# pocket_scope_complete_adc_v0001.net
KiCad netlist of a schematic drawn in EAGLE
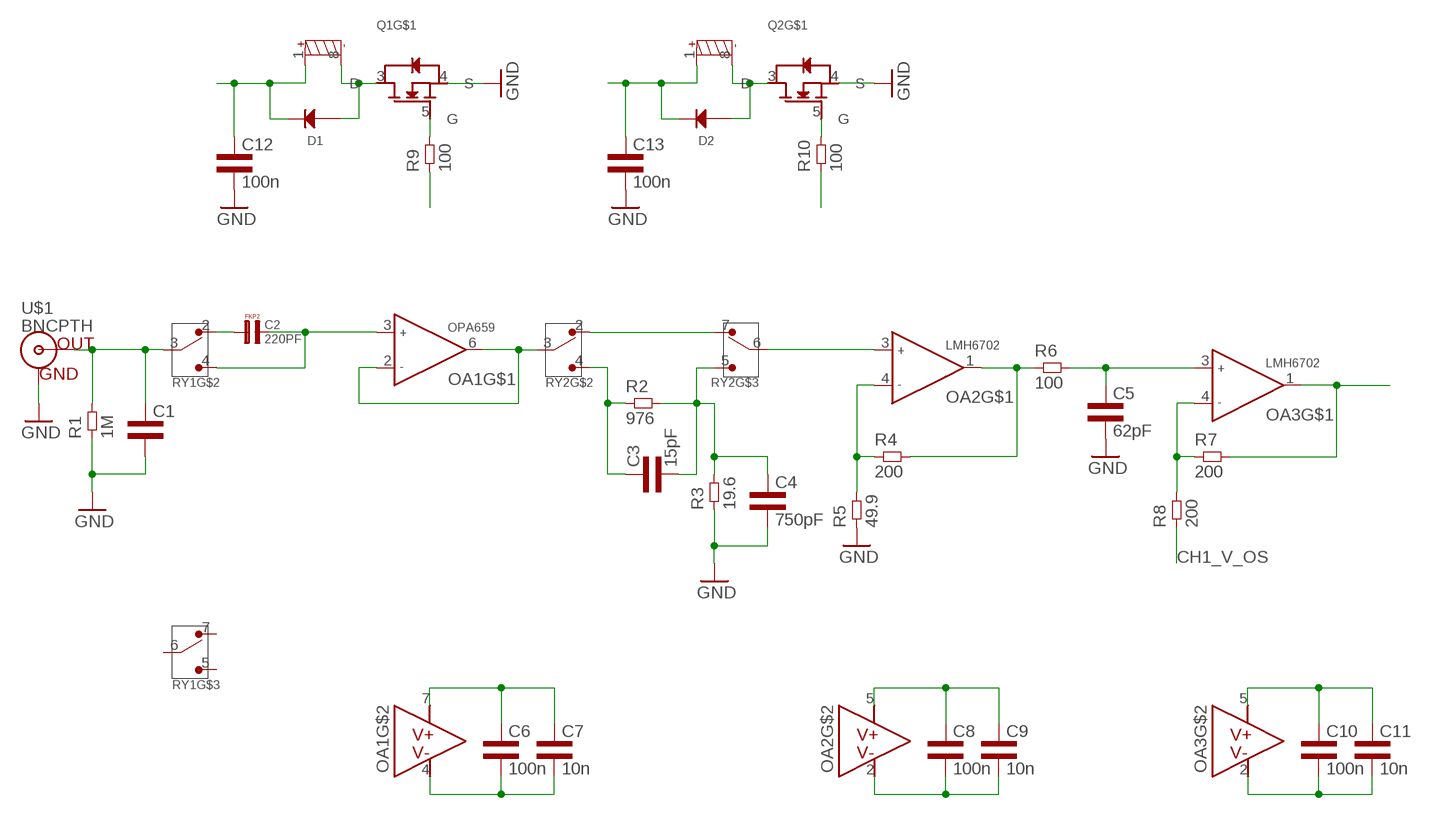
[diagram p0: schematic, sheet 1]

(export (version "E")
  (design (tool "Eeschema 10.0.6"))
  (components
    (comp (ref "C1")
      (value "CAP0603L3")
      (footprint "eagle-import:0603L3")
      (libsource (lib "eagle-import") (part "CAP0603L3"))
    )
    (comp (ref "C2")
      (value "220PF")
      (footprint "eagle-import:R5B4K5")
      (libsource (lib "eagle-import") (part "220PF"))
    )
    (comp (ref "C3")
      (value "15pF")
      (footprint "eagle-import:0603L3")
      (libsource (lib "eagle-import") (part "CAP0603L3"))
    )
    (comp (ref "C4")
      (value "750pF")
      (footprint "eagle-import:0603L3")
      (libsource (lib "eagle-import") (part "CAP0603L3"))
    )
    (comp (ref "C5")
      (value "62pF")
      (footprint "eagle-import:0603L3")
      (libsource (lib "eagle-import") (part "CAP0603L3"))
    )
    (comp (ref "C6")
      (value "100n")
      (footprint "eagle-import:0603L3")
      (libsource (lib "eagle-import") (part "CAP0603L3"))
    )
    (comp (ref "C7")
      (value "10n")
      (footprint "eagle-import:0603L3")
      (libsource (lib "eagle-import") (part "CAP0603L3"))
    )
    (comp (ref "C8")
      (value "100n")
      (footprint "eagle-import:0603L3")
      (libsource (lib "eagle-import") (part "CAP0603L3"))
    )
    (comp (ref "C9")
      (value "10n")
      (footprint "eagle-import:0603L3")
      (libsource (lib "eagle-import") (part "CAP0603L3"))
    )
    (comp (ref "C10")
      (value "100n")
      (footprint "eagle-import:0603L3")
      (libsource (lib "eagle-import") (part "CAP0603L3"))
    )
    (comp (ref "C11")
      (value "10n")
      (footprint "eagle-import:0603L3")
      (libsource (lib "eagle-import") (part "CAP0603L3"))
    )
    (comp (ref "C12")
      (value "100n")
      (footprint "eagle-import:0603L3")
      (libsource (lib "eagle-import") (part "CAP0603L3"))
    )
    (comp (ref "C13")
      (value "100n")
      (footprint "eagle-import:0603L3")
      (libsource (lib "eagle-import") (part "CAP0603L3"))
    )
    (comp (ref "D1")
      (value "DIODESMA")
      (footprint "eagle-import:SMA-2")
      (libsource (lib "eagle-import") (part "DIODESMA"))
    )
    (comp (ref "D2")
      (value "DIODESMA")
      (footprint "eagle-import:SMA-2")
      (libsource (lib "eagle-import") (part "DIODESMA"))
    )
    (comp (ref "OA1")
      (value "OPA659")
      (footprint "eagle-import:S-PVSON-N8")
      (libsource (lib "eagle-import") (part "OPA659DRB"))
    )
    (comp (ref "OA2")
      (value "LMH6702")
      (footprint "eagle-import:R-PDSO-G5")
      (libsource (lib "eagle-import") (part "OPA659DBV"))
    )
    (comp (ref "OA3")
      (value "LMH6702")
      (footprint "eagle-import:R-PDSO-G5")
      (libsource (lib "eagle-import") (part "OPA659DBV"))
    )
    (comp (ref "Q1")
      (value "2N7002DWA")
      (footprint "eagle-import:SC70")
      (libsource (lib "eagle-import") (part "2N7002DWA"))
    )
    (comp (ref "Q2")
      (value "2N7002DWA")
      (footprint "eagle-import:SC70")
      (libsource (lib "eagle-import") (part "2N7002DWA"))
    )
    (comp (ref "R1")
      (value "1M")
      (footprint "eagle-import:0603L3")
      (libsource (lib "eagle-import") (part "RES0603L3"))
    )
    (comp (ref "R2")
      (value "976")
      (footprint "eagle-import:0603L3")
      (libsource (lib "eagle-import") (part "RES0603L3"))
    )
    (comp (ref "R3")
      (value "19.6")
      (footprint "eagle-import:0603L3")
      (libsource (lib "eagle-import") (part "RES0603L3"))
    )
    (comp (ref "R4")
      (value "200")
      (footprint "eagle-import:0603L3")
      (libsource (lib "eagle-import") (part "RES0603L3"))
    )
    (comp (ref "R5")
      (value "49.9")
      (footprint "eagle-import:0603L3")
      (libsource (lib "eagle-import") (part "RES0603L3"))
    )
    (comp (ref "R6")
      (value "100")
      (footprint "eagle-import:0603L3")
      (libsource (lib "eagle-import") (part "RES0603L3"))
    )
    (comp (ref "R7")
      (value "200")
      (footprint "eagle-import:0603L3")
      (libsource (lib "eagle-import") (part "RES0603L3"))
    )
    (comp (ref "R8")
      (value "200")
      (footprint "eagle-import:0603L3")
      (libsource (lib "eagle-import") (part "RES0603L3"))
    )
    (comp (ref "R9")
      (value "100")
      (footprint "eagle-import:0603L3")
      (libsource (lib "eagle-import") (part "RES0603L3"))
    )
    (comp (ref "R10")
      (value "100")
      (footprint "eagle-import:0603L3")
      (libsource (lib "eagle-import") (part "RES0603L3"))
    )
    (comp (ref "RY1")
      (value "RELAY_SMD")
      (footprint "eagle-import:G6J-2FL-Y")
      (libsource (lib "eagle-import") (part "RELAY_SMD"))
    )
    (comp (ref "RY2")
      (value "RELAY_SMD")
      (footprint "eagle-import:G6J-2FL-Y")
      (libsource (lib "eagle-import") (part "RELAY_SMD"))
    )
    (comp (ref "U$1")
      (value "BNCPTH")
      (footprint "eagle-import:BNC")
      (libsource (lib "eagle-import") (part "BNCPTH"))
    )
  )
  (nets
    (net (code "1") (name "/CH1_V_OS") (class "Default")
      (node (ref "R8") (pin "P$1") (pinfunction "1_P$1") (pintype "bidirectional"))
    )
    (net (code "2") (name "GND") (class "Default")
      (node (ref "C1") (pin "P$2") (pinfunction "2_P$2") (pintype "bidirectional"))
      (node (ref "C12") (pin "P$2") (pinfunction "2_P$2") (pintype "bidirectional"))
      (node (ref "C13") (pin "P$2") (pinfunction "2_P$2") (pintype "bidirectional"))
      (node (ref "C4") (pin "P$2") (pinfunction "2_P$2") (pintype "bidirectional"))
      (node (ref "C5") (pin "P$2") (pinfunction "2_P$2") (pintype "bidirectional"))
      (node (ref "Q1") (pin "4") (pinfunction "S_4") (pintype "bidirectional"))
      (node (ref "Q2") (pin "4") (pinfunction "S_4") (pintype "bidirectional"))
      (node (ref "R1") (pin "P$1") (pinfunction "1_P$1") (pintype "bidirectional"))
      (node (ref "R3") (pin "P$1") (pinfunction "1_P$1") (pintype "bidirectional"))
      (node (ref "R5") (pin "P$1") (pinfunction "1_P$1") (pintype "bidirectional"))
      (node (ref "U$1") (pin "GND") (pinfunction "GND_GND") (pintype "bidirectional"))
    )
    (net (code "3") (name "Net-(C1-1)") (class "Default")
      (node (ref "C1") (pin "P$1") (pinfunction "1_P$1") (pintype "bidirectional"))
      (node (ref "R1") (pin "P$2") (pinfunction "2_P$2") (pintype "bidirectional"))
      (node (ref "RY1") (pin "3") (pinfunction "D_3") (pintype "bidirectional"))
      (node (ref "U$1") (pin "S") (pinfunction "OUT_S") (pintype "bidirectional"))
    )
    (net (code "4") (name "Net-(C3-1)") (class "Default")
      (node (ref "C3") (pin "P$1") (pinfunction "1_P$1") (pintype "bidirectional"))
      (node (ref "R2") (pin "P$1") (pinfunction "1_P$1") (pintype "bidirectional"))
      (node (ref "RY2") (pin "4") (pinfunction "T2_4") (pintype "bidirectional"))
    )
    (net (code "5") (name "Net-(C3-2)") (class "Default")
      (node (ref "C3") (pin "P$2") (pinfunction "2_P$2") (pintype "bidirectional"))
      (node (ref "C4") (pin "P$1") (pinfunction "1_P$1") (pintype "bidirectional"))
      (node (ref "R2") (pin "P$2") (pinfunction "2_P$2") (pintype "bidirectional"))
      (node (ref "R3") (pin "P$2") (pinfunction "2_P$2") (pintype "bidirectional"))
      (node (ref "RY2") (pin "5") (pinfunction "T2_5") (pintype "bidirectional"))
    )
    (net (code "6") (name "Net-(C5-1)") (class "Default")
      (node (ref "C5") (pin "P$1") (pinfunction "1_P$1") (pintype "bidirectional"))
      (node (ref "OA3") (pin "3") (pinfunction "INA+_3") (pintype "bidirectional"))
      (node (ref "R6") (pin "P$2") (pinfunction "2_P$2") (pintype "bidirectional"))
    )
    (net (code "7") (name "Net-(C6-1)") (class "Default")
      (node (ref "C6") (pin "P$1") (pinfunction "1_P$1") (pintype "bidirectional"))
      (node (ref "C7") (pin "P$1") (pinfunction "1_P$1") (pintype "bidirectional"))
      (node (ref "OA1") (pin "7") (pinfunction "V+_7") (pintype "power_in"))
    )
    (net (code "8") (name "Net-(C6-2)") (class "Default")
      (node (ref "C6") (pin "P$2") (pinfunction "2_P$2") (pintype "bidirectional"))
      (node (ref "C7") (pin "P$2") (pinfunction "2_P$2") (pintype "bidirectional"))
      (node (ref "OA1") (pin "4") (pinfunction "V-_4") (pintype "power_in"))
    )
    (net (code "9") (name "Net-(C8-1)") (class "Default")
      (node (ref "C8") (pin "P$1") (pinfunction "1_P$1") (pintype "bidirectional"))
      (node (ref "C9") (pin "P$1") (pinfunction "1_P$1") (pintype "bidirectional"))
      (node (ref "OA2") (pin "5") (pinfunction "V+_5") (pintype "power_in"))
    )
    (net (code "10") (name "Net-(C8-2)") (class "Default")
      (node (ref "C8") (pin "P$2") (pinfunction "2_P$2") (pintype "bidirectional"))
      (node (ref "C9") (pin "P$2") (pinfunction "2_P$2") (pintype "bidirectional"))
      (node (ref "OA2") (pin "2") (pinfunction "V-_2") (pintype "power_in"))
    )
    (net (code "11") (name "Net-(C10-1)") (class "Default")
      (node (ref "C10") (pin "P$1") (pinfunction "1_P$1") (pintype "bidirectional"))
      (node (ref "C11") (pin "P$1") (pinfunction "1_P$1") (pintype "bidirectional"))
      (node (ref "OA3") (pin "5") (pinfunction "V+_5") (pintype "power_in"))
    )
    (net (code "12") (name "Net-(C10-2)") (class "Default")
      (node (ref "C10") (pin "P$2") (pinfunction "2_P$2") (pintype "bidirectional"))
      (node (ref "C11") (pin "P$2") (pinfunction "2_P$2") (pintype "bidirectional"))
      (node (ref "OA3") (pin "2") (pinfunction "V-_2") (pintype "power_in"))
    )
    (net (code "13") (name "Net-(C12-1)") (class "Default")
      (node (ref "C12") (pin "P$1") (pinfunction "1_P$1") (pintype "bidirectional"))
      (node (ref "D1") (pin "2") (pinfunction "CATHODE_2") (pintype "bidirectional"))
      (node (ref "RY1") (pin "1") (pinfunction "COIL_+_1") (pintype "bidirectional"))
    )
    (net (code "14") (name "Net-(C13-1)") (class "Default")
      (node (ref "C13") (pin "P$1") (pinfunction "1_P$1") (pintype "bidirectional"))
      (node (ref "D2") (pin "2") (pinfunction "CATHODE_2") (pintype "bidirectional"))
      (node (ref "RY2") (pin "1") (pinfunction "COIL_+_1") (pintype "bidirectional"))
    )
    (net (code "15") (name "Net-(D1-ANODE)") (class "Default")
      (node (ref "D1") (pin "1") (pinfunction "ANODE_1") (pintype "bidirectional"))
      (node (ref "Q1") (pin "3") (pinfunction "D_3") (pintype "bidirectional"))
      (node (ref "RY1") (pin "8") (pinfunction "COIL_-_8") (pintype "bidirectional"))
    )
    (net (code "16") (name "Net-(D2-ANODE)") (class "Default")
      (node (ref "D2") (pin "1") (pinfunction "ANODE_1") (pintype "bidirectional"))
      (node (ref "Q2") (pin "3") (pinfunction "D_3") (pintype "bidirectional"))
      (node (ref "RY2") (pin "8") (pinfunction "COIL_-_8") (pintype "bidirectional"))
    )
    (net (code "17") (name "Net-(OA1A-INA+)") (class "Default")
      (node (ref "C2") (pin "2") (pinfunction "2_2") (pintype "passive"))
      (node (ref "OA1") (pin "3") (pinfunction "INA+_3") (pintype "bidirectional"))
      (node (ref "RY1") (pin "4") (pinfunction "T2_4") (pintype "bidirectional"))
    )
    (net (code "18") (name "Net-(OA1A-INA-)") (class "Default")
      (node (ref "OA1") (pin "2") (pinfunction "INA-_2") (pintype "bidirectional"))
      (node (ref "OA1") (pin "6") (pinfunction "OUTA_6") (pintype "bidirectional"))
      (node (ref "RY2") (pin "3") (pinfunction "D_3") (pintype "bidirectional"))
    )
    (net (code "19") (name "Net-(OA2A-INA+)") (class "Default")
      (node (ref "OA2") (pin "3") (pinfunction "INA+_3") (pintype "bidirectional"))
      (node (ref "RY2") (pin "6") (pinfunction "D_6") (pintype "bidirectional"))
    )
    (net (code "20") (name "Net-(OA2A-INA-)") (class "Default")
      (node (ref "OA2") (pin "4") (pinfunction "INA-_4") (pintype "bidirectional"))
      (node (ref "R4") (pin "P$1") (pinfunction "1_P$1") (pintype "bidirectional"))
      (node (ref "R5") (pin "P$2") (pinfunction "2_P$2") (pintype "bidirectional"))
    )
    (net (code "21") (name "Net-(OA2A-OUTA)") (class "Default")
      (node (ref "OA2") (pin "1") (pinfunction "OUTA_1") (pintype "bidirectional"))
      (node (ref "R4") (pin "P$2") (pinfunction "2_P$2") (pintype "bidirectional"))
      (node (ref "R6") (pin "P$1") (pinfunction "1_P$1") (pintype "bidirectional"))
    )
    (net (code "22") (name "Net-(OA3A-INA-)") (class "Default")
      (node (ref "OA3") (pin "4") (pinfunction "INA-_4") (pintype "bidirectional"))
      (node (ref "R7") (pin "P$1") (pinfunction "1_P$1") (pintype "bidirectional"))
      (node (ref "R8") (pin "P$2") (pinfunction "2_P$2") (pintype "bidirectional"))
    )
    (net (code "23") (name "Net-(OA3A-OUTA)") (class "Default")
      (node (ref "OA3") (pin "1") (pinfunction "OUTA_1") (pintype "bidirectional"))
      (node (ref "R7") (pin "P$2") (pinfunction "2_P$2") (pintype "bidirectional"))
    )
    (net (code "24") (name "Net-(Q1A-G)") (class "Default")
      (node (ref "Q1") (pin "5") (pinfunction "G_5") (pintype "bidirectional"))
      (node (ref "R9") (pin "P$2") (pinfunction "2_P$2") (pintype "bidirectional"))
    )
    (net (code "25") (name "Net-(Q2A-G)") (class "Default")
      (node (ref "Q2") (pin "5") (pinfunction "G_5") (pintype "bidirectional"))
      (node (ref "R10") (pin "P$2") (pinfunction "2_P$2") (pintype "bidirectional"))
    )
    (net (code "26") (name "Net-(RY1B-T1)") (class "Default")
      (node (ref "C2") (pin "1") (pinfunction "1_1") (pintype "passive"))
      (node (ref "RY1") (pin "2") (pinfunction "T1_2") (pintype "bidirectional"))
    )
    (net (code "27") (name "Net-(RY2B-T1)") (class "Default")
      (node (ref "RY2") (pin "2") (pinfunction "T1_2") (pintype "bidirectional"))
      (node (ref "RY2") (pin "7") (pinfunction "T1_7") (pintype "bidirectional"))
    )
    (net (code "28") (name "unconnected-(R9-1-PadP$1)") (class "Default")
      (node (ref "R9") (pin "P$1") (pinfunction "1_P$1") (pintype "bidirectional"))
    )
    (net (code "29") (name "unconnected-(R10-1-PadP$1)") (class "Default")
      (node (ref "R10") (pin "P$1") (pinfunction "1_P$1") (pintype "bidirectional"))
    )
    (net (code "30") (name "unconnected-(RY1C-D-Pad6)") (class "Default")
      (node (ref "RY1") (pin "6") (pinfunction "D_6") (pintype "bidirectional"))
    )
    (net (code "31") (name "unconnected-(RY1C-T1-Pad7)") (class "Default")
      (node (ref "RY1") (pin "7") (pinfunction "T1_7") (pintype "bidirectional"))
    )
    (net (code "32") (name "unconnected-(RY1C-T2-Pad5)") (class "Default")
      (node (ref "RY1") (pin "5") (pinfunction "T2_5") (pintype "bidirectional"))
    )
  )
)
